# Sheet_1_2022-07-13.net
KiCad netlist of a schematic drawn in Altium Designer
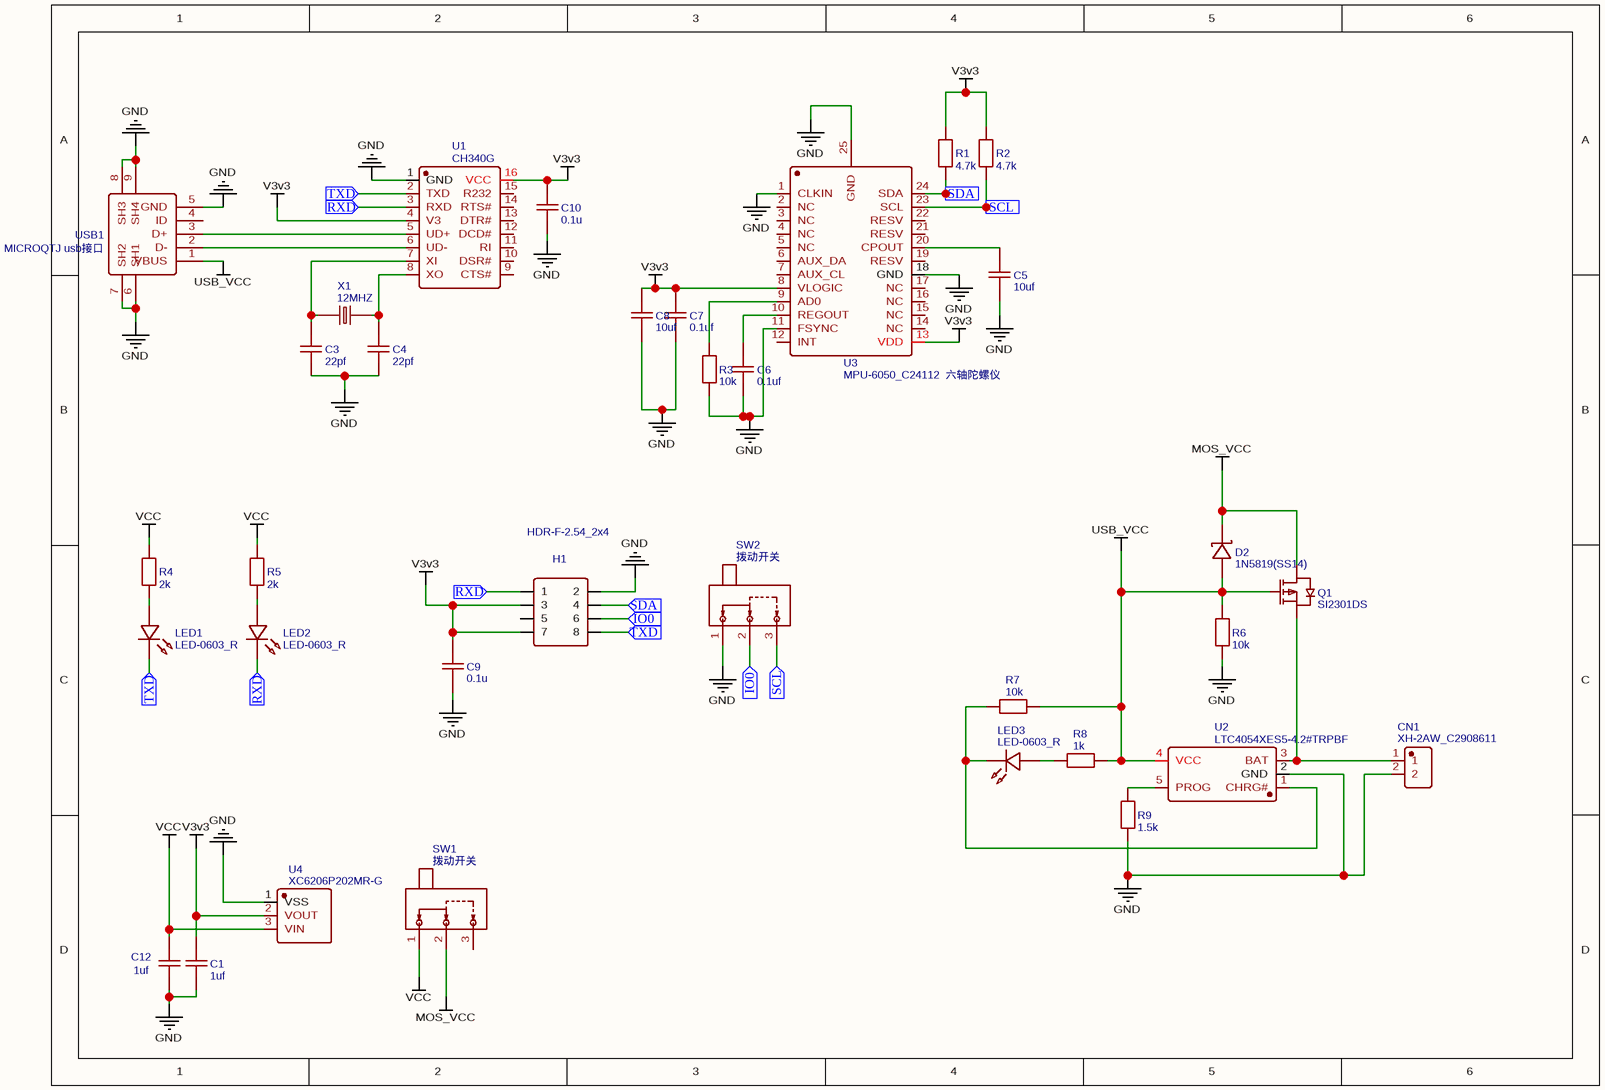
[diagram p0: Sheet_1_2022-07-13.schdoc]

(export (version "E")
  (design (tool "Eeschema 10.0.6"))
  (components
    (comp (ref "C1")
      (value "1uf")
      (fields (field (name "CONTRIBUTOR") "LCEDA_Lib"))
      (libsource (lib "altium-import") (part "root_3_1uf_"))
    )
    (comp (ref "C3")
      (value "22pf")
      (fields (field (name "CONTRIBUTOR") "LCEDA_Lib"))
      (libsource (lib "altium-import") (part "root_1_22pf_"))
    )
    (comp (ref "C4")
      (value "22pf")
      (fields (field (name "CONTRIBUTOR") "LCEDA_Lib"))
      (libsource (lib "altium-import") (part "root_1_22pf_"))
    )
    (comp (ref "C5")
      (value "10uf")
      (fields (field (name "CONTRIBUTOR") "LCEDA_Lib"))
      (libsource (lib "altium-import") (part "root_1_10uf_"))
    )
    (comp (ref "C6")
      (value "0.1uf")
      (fields (field (name "CONTRIBUTOR") "LCEDA_Lib"))
      (libsource (lib "altium-import") (part "root_1_0.1uf_"))
    )
    (comp (ref "C7")
      (value "0.1uf")
      (fields (field (name "CONTRIBUTOR") "LCEDA_Lib"))
      (libsource (lib "altium-import") (part "root_1_0.1uf_"))
    )
    (comp (ref "C8")
      (value "10uf")
      (fields (field (name "CONTRIBUTOR") "LCEDA_Lib"))
      (libsource (lib "altium-import") (part "root_1_10uf_"))
    )
    (comp (ref "C9")
      (value "0.1u")
      (fields (field (name "CONTRIBUTOR") "LCEDA_Lib"))
      (libsource (lib "altium-import") (part "root_1_0.1u_"))
    )
    (comp (ref "C10")
      (value "0.1u")
      (fields (field (name "CONTRIBUTOR") "LCEDA_Lib"))
      (libsource (lib "altium-import") (part "root_1_0.1u_"))
    )
    (comp (ref "C12")
      (value "1uf")
      (fields (field (name "CONTRIBUTOR") "LCEDA_Lib"))
      (libsource (lib "altium-import") (part "root_3_1uf_"))
    )
    (comp (ref "CN1")
      (value "XH-2AW_C2908611")
      (fields
        (field (name "BOM_SUPPLIER PART") "C2908611")
        (field (name "BOM_MANUFACTURER PART") "XH-2AW")
        (field (name "CONTRIBUTOR") "LCSC")
      )
      (libsource (lib "altium-import") (part "root_0_XH-2AW_C2908611_"))
    )
    (comp (ref "D2")
      (value "1N5819(SS14)")
      (fields (field (name "BOM_SUPPLIER PART") "C489138") (field (name "CONTRIBUTOR") "LCSC"))
      (libsource (lib "altium-import") (part "root_3_1N5819(SS14)_"))
    )
    (comp (ref "H1")
      (value "HDR-F-2.54_2x4")
      (fields (field (name "BOM_SUPPLIER PART") "C239344") (field (name "CONTRIBUTOR") "LCEDA_Lib"))
      (libsource (lib "altium-import") (part "root_0_HDR-F-2.54_2x4_"))
    )
    (comp (ref "LED1")
      (value "LED-0603_R")
      (fields
        (field (name "BOM_MANUFACTURER PART") "19-217/R6C-AL1M2VY/3T")
        (field (name "BOM_SUPPLIER PART") "C72044")
        (field (name "CONTRIBUTOR") "LCEDA_01")
      )
      (libsource (lib "altium-import") (part "root_3_LED-0603_R_"))
    )
    (comp (ref "LED2")
      (value "LED-0603_R")
      (fields
        (field (name "BOM_MANUFACTURER PART") "19-217/R6C-AL1M2VY/3T")
        (field (name "BOM_SUPPLIER PART") "C72044")
        (field (name "CONTRIBUTOR") "LCEDA_01")
      )
      (libsource (lib "altium-import") (part "root_3_LED-0603_R_"))
    )
    (comp (ref "LED3")
      (value "LED-0603_R")
      (fields
        (field (name "BOM_MANUFACTURER PART") "19-217/R6C-AL1M2VY/3T")
        (field (name "BOM_SUPPLIER PART") "C72044")
        (field (name "CONTRIBUTOR") "LCEDA_01")
      )
      (libsource (lib "altium-import") (part "root_2_LED-0603_R_"))
    )
    (comp (ref "Q1")
      (value "SI2301DS")
      (fields (field (name "BOM_SUPPLIER PART") "C2841444") (field (name "CONTRIBUTOR") "LCSC"))
      (libsource (lib "altium-import") (part "root_0_SI2301DS_"))
    )
    (comp (ref "R1")
      (value "4.7k")
      (fields (field (name "CONTRIBUTOR") "LCEDA_Lib"))
      (libsource (lib "altium-import") (part "root_1_4.7k_"))
    )
    (comp (ref "R2")
      (value "4.7k")
      (fields (field (name "CONTRIBUTOR") "LCEDA_Lib"))
      (libsource (lib "altium-import") (part "root_1_4.7k_"))
    )
    (comp (ref "R3")
      (value "10k")
      (fields (field (name "CONTRIBUTOR") "LCEDA_Lib"))
      (libsource (lib "altium-import") (part "root_1_10k_"))
    )
    (comp (ref "R4")
      (value "2k")
      (fields (field (name "CONTRIBUTOR") "LCEDA_Lib"))
      (libsource (lib "altium-import") (part "root_1_2k_"))
    )
    (comp (ref "R5")
      (value "2k")
      (fields (field (name "CONTRIBUTOR") "LCEDA_Lib"))
      (libsource (lib "altium-import") (part "root_1_2k_"))
    )
    (comp (ref "R6")
      (value "10k")
      (fields (field (name "CONTRIBUTOR") "LCEDA_Lib"))
      (libsource (lib "altium-import") (part "root_3_10k_"))
    )
    (comp (ref "R7")
      (value "10k")
      (fields (field (name "CONTRIBUTOR") "LCEDA_Lib"))
      (libsource (lib "altium-import") (part "root_0_10k_"))
    )
    (comp (ref "R8")
      (value "1k")
      (fields (field (name "CONTRIBUTOR") "LCEDA_Lib"))
      (libsource (lib "altium-import") (part "root_0_1k_"))
    )
    (comp (ref "R9")
      (value "1.5k")
      (fields (field (name "CONTRIBUTOR") "LCEDA_Lib"))
      (libsource (lib "altium-import") (part "root_1_1.5k_"))
    )
    (comp (ref "SW1")
      (value "拨动开关")
      (fields
        (field (name "BOM_SUPPLIER PART") "C2876014")
        (field (name "BOM_MANUFACTURER PART") "SS-12D01-G040")
        (field (name "CONTRIBUTOR") "LCSC")
      )
      (libsource (lib "altium-import") (part "root_0_拨动开关_"))
    )
    (comp (ref "SW2")
      (value "拨动开关")
      (fields
        (field (name "BOM_SUPPLIER PART") "C2876014")
        (field (name "BOM_MANUFACTURER PART") "SS-12D01-G040")
        (field (name "CONTRIBUTOR") "LCSC")
      )
      (libsource (lib "altium-import") (part "root_0_拨动开关_"))
    )
    (comp (ref "U1")
      (value "CH340G")
      (fields (field (name "BOM_SUPPLIER PART") "C14267"))
      (libsource (lib "altium-import") (part "root_0_CH340G_"))
    )
    (comp (ref "U2")
      (value "LTC4054XES5-4.2#TRPBF")
      (fields (field (name "BOM_SUPPLIER PART") "C687179") (field (name "CONTRIBUTOR") "lcsc"))
      (libsource (lib "altium-import") (part "root_2_LTC4054XES5-4.2#TRPBF_"))
    )
    (comp (ref "U3")
      (value "MPU-6050_C24112  六轴陀螺仪")
      (fields (field (name "BOM_MANUFACTURER PART") "MPU-6050") (field (name "BOM_SUPPLIER PART") "C24112"))
      (libsource (lib "altium-import") (part "root_0_MPU-6050_C24112  六轴陀螺仪_"))
    )
    (comp (ref "U4")
      (value "XC6206P202MR-G")
      (fields (field (name "BOM_SUPPLIER PART") "C2891260") (field (name "CONTRIBUTOR") "LCSC"))
      (libsource (lib "altium-import") (part "root_0_XC6206P202MR-G_"))
    )
    (comp (ref "USB1")
      (value "MICROQTJ usb接口")
      (fields
        (field (name "BOM_SUPPLIER PART") "C404968")
        (field (name "BOM_MANUFACTURER PART") "MicroQTJ")
        (field (name "CONTRIBUTOR") "LCSC")
      )
      (libsource (lib "altium-import") (part "root_2_MICROQTJ usb接口_"))
    )
    (comp (ref "X1")
      (value "12MHZ")
      (fields
        (field (name "BOM_SUPPLIER PART") "C295091")
        (field (name "BOM_MANUFACTURER PART") "XJHCELNANF-12MHZ")
        (field (name "CONTRIBUTOR") "LCSC")
      )
      (libsource (lib "altium-import") (part "root_0_12MHZ_"))
    )
  )
  (nets
    (net (code "1") (name "/IO0") (class "Default")
      (node (ref "H1") (pin "6") (pinfunction "6_6") (pintype "passive"))
      (node (ref "SW2") (pin "2") (pinfunction "2_2") (pintype "passive"))
    )
    (net (code "2") (name "/RXD") (class "Default")
      (node (ref "H1") (pin "1") (pinfunction "1_1") (pintype "passive"))
      (node (ref "LED2") (pin "2") (pinfunction "2_2") (pintype "passive"))
      (node (ref "U1") (pin "3") (pinfunction "RXD_3") (pintype "passive"))
    )
    (net (code "3") (name "/SCL") (class "Default")
      (node (ref "R2") (pin "1") (pinfunction "1_1") (pintype "passive"))
      (node (ref "SW2") (pin "3") (pinfunction "3_3") (pintype "passive"))
      (node (ref "U3") (pin "23") (pinfunction "SCL_23") (pintype "passive"))
    )
    (net (code "4") (name "/SDA") (class "Default")
      (node (ref "H1") (pin "4") (pinfunction "4_4") (pintype "passive"))
      (node (ref "R1") (pin "1") (pinfunction "1_1") (pintype "passive"))
      (node (ref "U3") (pin "24") (pinfunction "SDA_24") (pintype "passive"))
    )
    (net (code "5") (name "/TXD") (class "Default")
      (node (ref "H1") (pin "8") (pinfunction "8_8") (pintype "passive"))
      (node (ref "LED1") (pin "2") (pinfunction "2_2") (pintype "passive"))
      (node (ref "U1") (pin "2") (pinfunction "TXD_2") (pintype "passive"))
    )
    (net (code "6") (name "GND") (class "Default")
      (node (ref "C1") (pin "2") (pinfunction "2_2") (pintype "passive"))
      (node (ref "C10") (pin "1") (pinfunction "1_1") (pintype "passive"))
      (node (ref "C12") (pin "2") (pinfunction "2_2") (pintype "passive"))
      (node (ref "C3") (pin "1") (pinfunction "1_1") (pintype "passive"))
      (node (ref "C4") (pin "1") (pinfunction "1_1") (pintype "passive"))
      (node (ref "C5") (pin "1") (pinfunction "1_1") (pintype "passive"))
      (node (ref "C6") (pin "1") (pinfunction "1_1") (pintype "passive"))
      (node (ref "C7") (pin "1") (pinfunction "1_1") (pintype "passive"))
      (node (ref "C8") (pin "1") (pinfunction "1_1") (pintype "passive"))
      (node (ref "C9") (pin "1") (pinfunction "1_1") (pintype "passive"))
      (node (ref "CN1") (pin "2") (pinfunction "2_2") (pintype "passive"))
      (node (ref "H1") (pin "2") (pinfunction "2_2") (pintype "passive"))
      (node (ref "R3") (pin "1") (pinfunction "1_1") (pintype "passive"))
      (node (ref "R6") (pin "2") (pinfunction "2_2") (pintype "passive"))
      (node (ref "R9") (pin "1") (pinfunction "1_1") (pintype "passive"))
      (node (ref "SW2") (pin "1") (pinfunction "1_1") (pintype "passive"))
      (node (ref "U1") (pin "1") (pinfunction "GND_1") (pintype "passive"))
      (node (ref "U2") (pin "2") (pinfunction "GND_2") (pintype "passive"))
      (node (ref "U3") (pin "1") (pinfunction "CLKIN_1") (pintype "passive"))
      (node (ref "U3") (pin "11") (pinfunction "FSYNC_11") (pintype "passive"))
      (node (ref "U3") (pin "18") (pinfunction "GND_18") (pintype "passive"))
      (node (ref "U3") (pin "25") (pinfunction "GND_25") (pintype "passive"))
      (node (ref "U4") (pin "1") (pinfunction "VSS_1") (pintype "passive"))
      (node (ref "USB1") (pin "5") (pinfunction "GND_5") (pintype "passive"))
      (node (ref "USB1") (pin "6") (pinfunction "SH1_6") (pintype "passive"))
      (node (ref "USB1") (pin "7") (pinfunction "SH2_7") (pintype "passive"))
      (node (ref "USB1") (pin "8") (pinfunction "SH3_8") (pintype "passive"))
      (node (ref "USB1") (pin "9") (pinfunction "SH4_9") (pintype "passive"))
    )
    (net (code "7") (name "MOS_VCC") (class "Default")
      (node (ref "D2") (pin "1") (pinfunction "C_1") (pintype "passive"))
      (node (ref "Q1") (pin "3") (pinfunction "D_3") (pintype "passive"))
      (node (ref "SW1") (pin "2") (pinfunction "2_2") (pintype "passive"))
    )
    (net (code "8") (name "Net-(LED1-Pad1)") (class "Default")
      (node (ref "LED1") (pin "1") (pinfunction "1_1") (pintype "passive"))
      (node (ref "R4") (pin "1") (pinfunction "1_1") (pintype "passive"))
    )
    (net (code "9") (name "Net-(LED2-Pad1)") (class "Default")
      (node (ref "LED2") (pin "1") (pinfunction "1_1") (pintype "passive"))
      (node (ref "R5") (pin "1") (pinfunction "1_1") (pintype "passive"))
    )
    (net (code "10") (name "Net-(LED3-Pad1)") (class "Default")
      (node (ref "LED3") (pin "1") (pinfunction "1_1") (pintype "passive"))
      (node (ref "R8") (pin "1") (pinfunction "1_1") (pintype "passive"))
    )
    (net (code "11") (name "Net-(Q1-S)") (class "Default")
      (node (ref "CN1") (pin "1") (pinfunction "1_1") (pintype "passive"))
      (node (ref "Q1") (pin "2") (pinfunction "S_2") (pintype "passive"))
      (node (ref "U2") (pin "3") (pinfunction "BAT_3") (pintype "passive"))
    )
    (net (code "12") (name "Net-(U1-UD+)") (class "Default")
      (node (ref "U1") (pin "5") (pinfunction "UD+_5") (pintype "passive"))
      (node (ref "USB1") (pin "3") (pinfunction "D+_3") (pintype "passive"))
    )
    (net (code "13") (name "Net-(U1-UD-)") (class "Default")
      (node (ref "U1") (pin "6") (pinfunction "UD-_6") (pintype "passive"))
      (node (ref "USB1") (pin "2") (pinfunction "D-_2") (pintype "passive"))
    )
    (net (code "14") (name "Net-(U1-XI)") (class "Default")
      (node (ref "C3") (pin "2") (pinfunction "2_2") (pintype "passive"))
      (node (ref "U1") (pin "7") (pinfunction "XI_7") (pintype "passive"))
      (node (ref "X1") (pin "1") (pinfunction "1_1") (pintype "passive"))
    )
    (net (code "15") (name "Net-(U1-XO)") (class "Default")
      (node (ref "C4") (pin "2") (pinfunction "2_2") (pintype "passive"))
      (node (ref "U1") (pin "8") (pinfunction "XO_8") (pintype "passive"))
      (node (ref "X1") (pin "2") (pinfunction "2_2") (pintype "passive"))
    )
    (net (code "16") (name "Net-(U2-CHRG#)") (class "Default")
      (node (ref "LED3") (pin "2") (pinfunction "2_2") (pintype "passive"))
      (node (ref "R7") (pin "1") (pinfunction "1_1") (pintype "passive"))
      (node (ref "U2") (pin "1") (pinfunction "CHRG#_1") (pintype "passive"))
    )
    (net (code "17") (name "Net-(U2-PROG)") (class "Default")
      (node (ref "R9") (pin "2") (pinfunction "2_2") (pintype "passive"))
      (node (ref "U2") (pin "5") (pinfunction "PROG_5") (pintype "passive"))
    )
    (net (code "18") (name "Net-(U3-AD0)") (class "Default")
      (node (ref "R3") (pin "2") (pinfunction "2_2") (pintype "passive"))
      (node (ref "U3") (pin "9") (pinfunction "AD0_9") (pintype "passive"))
    )
    (net (code "19") (name "Net-(U3-CPOUT)") (class "Default")
      (node (ref "C5") (pin "2") (pinfunction "2_2") (pintype "passive"))
      (node (ref "U3") (pin "20") (pinfunction "CPOUT_20") (pintype "passive"))
    )
    (net (code "20") (name "Net-(U3-REGOUT)") (class "Default")
      (node (ref "C6") (pin "2") (pinfunction "2_2") (pintype "passive"))
      (node (ref "U3") (pin "10") (pinfunction "REGOUT_10") (pintype "passive"))
    )
    (net (code "21") (name "USB_VCC") (class "Default")
      (node (ref "D2") (pin "2") (pinfunction "A_2") (pintype "passive"))
      (node (ref "Q1") (pin "1") (pinfunction "G_1") (pintype "passive"))
      (node (ref "R6") (pin "1") (pinfunction "1_1") (pintype "passive"))
      (node (ref "R7") (pin "2") (pinfunction "2_2") (pintype "passive"))
      (node (ref "R8") (pin "2") (pinfunction "2_2") (pintype "passive"))
      (node (ref "U2") (pin "4") (pinfunction "VCC_4") (pintype "passive"))
      (node (ref "USB1") (pin "1") (pinfunction "VBUS_1") (pintype "passive"))
    )
    (net (code "22") (name "V3v3") (class "Default")
      (node (ref "C1") (pin "1") (pinfunction "1_1") (pintype "passive"))
      (node (ref "C10") (pin "2") (pinfunction "2_2") (pintype "passive"))
      (node (ref "C7") (pin "2") (pinfunction "2_2") (pintype "passive"))
      (node (ref "C8") (pin "2") (pinfunction "2_2") (pintype "passive"))
      (node (ref "C9") (pin "2") (pinfunction "2_2") (pintype "passive"))
      (node (ref "H1") (pin "3") (pinfunction "3_3") (pintype "passive"))
      (node (ref "H1") (pin "7") (pinfunction "7_7") (pintype "passive"))
      (node (ref "R1") (pin "2") (pinfunction "2_2") (pintype "passive"))
      (node (ref "R2") (pin "2") (pinfunction "2_2") (pintype "passive"))
      (node (ref "U1") (pin "16") (pinfunction "VCC_16") (pintype "passive"))
      (node (ref "U1") (pin "4") (pinfunction "V3_4") (pintype "passive"))
      (node (ref "U3") (pin "13") (pinfunction "VDD_13") (pintype "passive"))
      (node (ref "U3") (pin "8") (pinfunction "VLOGIC_8") (pintype "passive"))
      (node (ref "U4") (pin "2") (pinfunction "VOUT_2") (pintype "passive"))
    )
    (net (code "23") (name "VCC") (class "Default")
      (node (ref "C12") (pin "1") (pinfunction "1_1") (pintype "passive"))
      (node (ref "R4") (pin "2") (pinfunction "2_2") (pintype "passive"))
      (node (ref "R5") (pin "2") (pinfunction "2_2") (pintype "passive"))
      (node (ref "SW1") (pin "1") (pinfunction "1_1") (pintype "passive"))
      (node (ref "U4") (pin "3") (pinfunction "VIN_3") (pintype "passive"))
    )
    (net (code "24") (name "unconnected-(H1-Pad5)") (class "Default")
      (node (ref "H1") (pin "5") (pinfunction "5_5") (pintype "passive"))
    )
    (net (code "25") (name "unconnected-(SW1-Pad3)") (class "Default")
      (node (ref "SW1") (pin "3") (pinfunction "3_3") (pintype "passive"))
    )
    (net (code "26") (name "unconnected-(U1-CTS#-Pad9)") (class "Default")
      (node (ref "U1") (pin "9") (pinfunction "CTS#_9") (pintype "passive"))
    )
    (net (code "27") (name "unconnected-(U1-DCD#-Pad12)") (class "Default")
      (node (ref "U1") (pin "12") (pinfunction "DCD#_12") (pintype "passive"))
    )
    (net (code "28") (name "unconnected-(U1-DSR#-Pad10)") (class "Default")
      (node (ref "U1") (pin "10") (pinfunction "DSR#_10") (pintype "passive"))
    )
    (net (code "29") (name "unconnected-(U1-DTR#-Pad13)") (class "Default")
      (node (ref "U1") (pin "13") (pinfunction "DTR#_13") (pintype "passive"))
    )
    (net (code "30") (name "unconnected-(U1-R232-Pad15)") (class "Default")
      (node (ref "U1") (pin "15") (pinfunction "R232_15") (pintype "passive"))
    )
    (net (code "31") (name "unconnected-(U1-RI-Pad11)") (class "Default")
      (node (ref "U1") (pin "11") (pinfunction "RI_11") (pintype "passive"))
    )
    (net (code "32") (name "unconnected-(U1-RTS#-Pad14)") (class "Default")
      (node (ref "U1") (pin "14") (pinfunction "RTS#_14") (pintype "passive"))
    )
    (net (code "33") (name "unconnected-(U3-AUX_CL-Pad7)") (class "Default")
      (node (ref "U3") (pin "7") (pinfunction "AUX_CL_7") (pintype "passive"))
    )
    (net (code "34") (name "unconnected-(U3-AUX_DA-Pad6)") (class "Default")
      (node (ref "U3") (pin "6") (pinfunction "AUX_DA_6") (pintype "passive"))
    )
    (net (code "35") (name "unconnected-(U3-INT-Pad12)") (class "Default")
      (node (ref "U3") (pin "12") (pinfunction "INT_12") (pintype "passive"))
    )
    (net (code "36") (name "unconnected-(U3-NC-Pad2)") (class "Default")
      (node (ref "U3") (pin "2") (pinfunction "NC_2") (pintype "passive"))
    )
    (net (code "37") (name "unconnected-(U3-NC-Pad3)") (class "Default")
      (node (ref "U3") (pin "3") (pinfunction "NC_3") (pintype "passive"))
    )
    (net (code "38") (name "unconnected-(U3-NC-Pad4)") (class "Default")
      (node (ref "U3") (pin "4") (pinfunction "NC_4") (pintype "passive"))
    )
    (net (code "39") (name "unconnected-(U3-NC-Pad5)") (class "Default")
      (node (ref "U3") (pin "5") (pinfunction "NC_5") (pintype "passive"))
    )
    (net (code "40") (name "unconnected-(U3-NC-Pad14)") (class "Default")
      (node (ref "U3") (pin "14") (pinfunction "NC_14") (pintype "passive"))
    )
    (net (code "41") (name "unconnected-(U3-NC-Pad15)") (class "Default")
      (node (ref "U3") (pin "15") (pinfunction "NC_15") (pintype "passive"))
    )
    (net (code "42") (name "unconnected-(U3-NC-Pad16)") (class "Default")
      (node (ref "U3") (pin "16") (pinfunction "NC_16") (pintype "passive"))
    )
    (net (code "43") (name "unconnected-(U3-NC-Pad17)") (class "Default")
      (node (ref "U3") (pin "17") (pinfunction "NC_17") (pintype "passive"))
    )
    (net (code "44") (name "unconnected-(U3-RESV-Pad19)") (class "Default")
      (node (ref "U3") (pin "19") (pinfunction "RESV_19") (pintype "passive"))
    )
    (net (code "45") (name "unconnected-(U3-RESV-Pad21)") (class "Default")
      (node (ref "U3") (pin "21") (pinfunction "RESV_21") (pintype "passive"))
    )
    (net (code "46") (name "unconnected-(U3-RESV-Pad22)") (class "Default")
      (node (ref "U3") (pin "22") (pinfunction "RESV_22") (pintype "passive"))
    )
    (net (code "47") (name "unconnected-(USB1-ID-Pad4)") (class "Default")
      (node (ref "USB1") (pin "4") (pinfunction "ID_4") (pintype "passive"))
    )
  )
)
